# ETH_PHY_RMII.net
KiCad netlist of a schematic drawn in Altium Designer
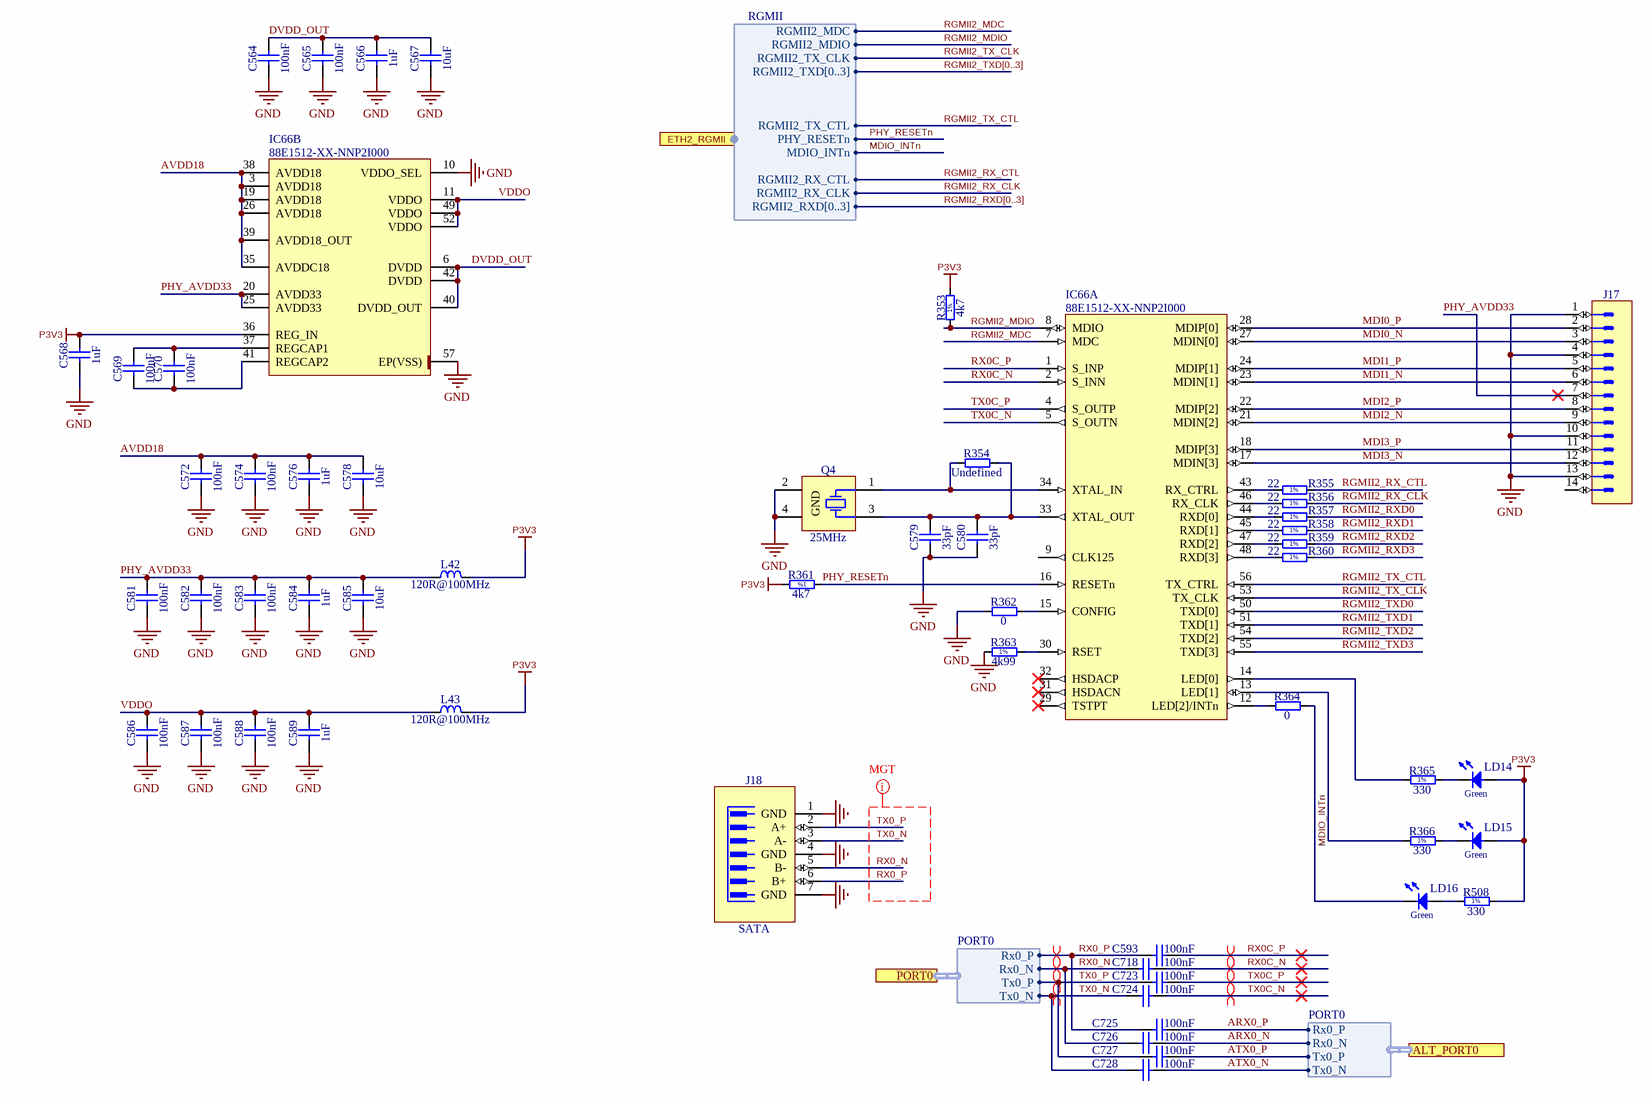
[diagram p0: ETH_PHY_RMII.SchDoc]

(export (version "E")
  (design (tool "Eeschema 10.0.6"))
  (components
    (comp (ref "C564")
      (value "100nF")
      (footprint "CAPC0603X33N")
      (description "Non-polarised capacitor")
      (fields
        (field (name "MANUFACTURER PART NUMBER") "CC0201_100NF_6.3V_10%_X5R")
        (field (name "MANUFACTURER") "GENERIC")
        (field (name "AUTHOR") "CERN DEM JLC")
      )
      (libsource (lib "Capacitors") (part "Capacitor - non polarized"))
    )
    (comp (ref "C565")
      (value "100nF")
      (footprint "CAPC0603X33N")
      (description "Non-polarised capacitor")
      (fields
        (field (name "MANUFACTURER PART NUMBER") "CC0201_100NF_6.3V_10%_X5R")
        (field (name "MANUFACTURER") "GENERIC")
        (field (name "AUTHOR") "CERN DEM JLC")
      )
      (libsource (lib "Capacitors") (part "Capacitor - non polarized"))
    )
    (comp (ref "C566")
      (value "1uF")
      (footprint "CAPC1005X55N")
      (description "Non-polarised capacitor")
      (fields
        (field (name "MANUFACTURER PART NUMBER") "CC0402_1UF_16V_10%_X5R")
        (field (name "MANUFACTURER") "GENERIC")
        (field (name "AUTHOR") "CERN DEM JLC")
      )
      (libsource (lib "Capacitors") (part "Capacitor - non polarized"))
    )
    (comp (ref "C567")
      (value "10uF")
      (footprint "CAPC1608X87N")
      (description "Non-polarised capacitor")
      (fields
        (field (name "MANUFACTURER PART NUMBER") "CC0603_10uF_6.3V_20%_X5R")
        (field (name "MANUFACTURER") "GENERIC")
        (field (name "AUTHOR") "CERN DEM JLC")
      )
      (libsource (lib "Capacitors") (part "Capacitor - non polarized"))
    )
    (comp (ref "C568")
      (value "1uF")
      (footprint "CAPC1005X55N")
      (description "Non-polarised capacitor")
      (fields
        (field (name "MANUFACTURER PART NUMBER") "CC0402_1UF_16V_10%_X5R")
        (field (name "MANUFACTURER") "GENERIC")
        (field (name "AUTHOR") "CERN DEM JLC")
      )
      (libsource (lib "Capacitors") (part "Capacitor - non polarized"))
    )
    (comp (ref "C569")
      (value "100nF")
      (footprint "CAPC0603X33N")
      (description "Non-polarised capacitor")
      (fields
        (field (name "MANUFACTURER PART NUMBER") "CC0201_100NF_6.3V_10%_X5R")
        (field (name "MANUFACTURER") "GENERIC")
        (field (name "AUTHOR") "CERN DEM JLC")
      )
      (libsource (lib "Capacitors") (part "Capacitor - non polarized"))
    )
    (comp (ref "C570")
      (value "100nF")
      (footprint "CAPC0603X33N")
      (description "Non-polarised capacitor")
      (fields
        (field (name "MANUFACTURER PART NUMBER") "CC0201_100NF_6.3V_10%_X5R")
        (field (name "MANUFACTURER") "GENERIC")
        (field (name "AUTHOR") "CERN DEM JLC")
      )
      (libsource (lib "Capacitors") (part "Capacitor - non polarized"))
    )
    (comp (ref "C572")
      (value "100nF")
      (footprint "CAPC0603X33N")
      (description "Non-polarised capacitor")
      (fields
        (field (name "MANUFACTURER PART NUMBER") "CC0201_100NF_6.3V_10%_X5R")
        (field (name "MANUFACTURER") "GENERIC")
        (field (name "AUTHOR") "CERN DEM JLC")
      )
      (libsource (lib "Capacitors") (part "Capacitor - non polarized"))
    )
    (comp (ref "C574")
      (value "100nF")
      (footprint "CAPC0603X33N")
      (description "Non-polarised capacitor")
      (fields
        (field (name "MANUFACTURER PART NUMBER") "CC0201_100NF_6.3V_10%_X5R")
        (field (name "MANUFACTURER") "GENERIC")
        (field (name "AUTHOR") "CERN DEM JLC")
      )
      (libsource (lib "Capacitors") (part "Capacitor - non polarized"))
    )
    (comp (ref "C576")
      (value "1uF")
      (footprint "CAPC1005X55N")
      (description "Non-polarised capacitor")
      (fields
        (field (name "MANUFACTURER PART NUMBER") "CC0402_1UF_16V_10%_X5R")
        (field (name "MANUFACTURER") "GENERIC")
        (field (name "AUTHOR") "CERN DEM JLC")
      )
      (libsource (lib "Capacitors") (part "Capacitor - non polarized"))
    )
    (comp (ref "C578")
      (value "10uF")
      (footprint "CAPC1608X87N")
      (description "Non-polarised capacitor")
      (fields
        (field (name "MANUFACTURER PART NUMBER") "CC0603_10uF_6.3V_20%_X5R")
        (field (name "MANUFACTURER") "GENERIC")
        (field (name "AUTHOR") "CERN DEM JLC")
      )
      (libsource (lib "Capacitors") (part "Capacitor - non polarized"))
    )
    (comp (ref "C579")
      (value "33pF")
      (footprint "CAPC1005X55N")
      (description "Non-polarised capacitor")
      (fields
        (field (name "PART NUMBER") "CC0402_33PF_50V_5%_C0G")
        (field (name "VOLTAGE") "50V")
        (field (name "AUTHOR") "CERN DEM JLC")
      )
      (libsource (lib "Capacitors") (part "Capacitor - non polarized"))
    )
    (comp (ref "C580")
      (value "33pF")
      (footprint "CAPC1005X55N")
      (description "Non-polarised capacitor")
      (fields
        (field (name "PART NUMBER") "CC0402_33PF_50V_5%_C0G")
        (field (name "VOLTAGE") "50V")
        (field (name "AUTHOR") "CERN DEM JLC")
      )
      (libsource (lib "Capacitors") (part "Capacitor - non polarized"))
    )
    (comp (ref "C581")
      (value "100nF")
      (footprint "CAPC0603X33N")
      (description "Non-polarised capacitor")
      (fields
        (field (name "MANUFACTURER PART NUMBER") "CC0201_100NF_6.3V_10%_X5R")
        (field (name "MANUFACTURER") "GENERIC")
        (field (name "AUTHOR") "CERN DEM JLC")
      )
      (libsource (lib "Capacitors") (part "Capacitor - non polarized"))
    )
    (comp (ref "C582")
      (value "100nF")
      (footprint "CAPC0603X33N")
      (description "Non-polarised capacitor")
      (fields
        (field (name "MANUFACTURER PART NUMBER") "CC0201_100NF_6.3V_10%_X5R")
        (field (name "MANUFACTURER") "GENERIC")
        (field (name "AUTHOR") "CERN DEM JLC")
      )
      (libsource (lib "Capacitors") (part "Capacitor - non polarized"))
    )
    (comp (ref "C583")
      (value "100nF")
      (footprint "CAPC0603X33N")
      (description "Non-polarised capacitor")
      (fields
        (field (name "MANUFACTURER PART NUMBER") "CC0201_100NF_6.3V_10%_X5R")
        (field (name "MANUFACTURER") "GENERIC")
        (field (name "AUTHOR") "CERN DEM JLC")
      )
      (libsource (lib "Capacitors") (part "Capacitor - non polarized"))
    )
    (comp (ref "C584")
      (value "1uF")
      (footprint "CAPC1005X55N")
      (description "Non-polarised capacitor")
      (fields
        (field (name "MANUFACTURER PART NUMBER") "CC0402_1UF_16V_10%_X5R")
        (field (name "MANUFACTURER") "GENERIC")
        (field (name "AUTHOR") "CERN DEM JLC")
      )
      (libsource (lib "Capacitors") (part "Capacitor - non polarized"))
    )
    (comp (ref "C585")
      (value "10uF")
      (footprint "CAPC1608X87N")
      (description "Non-polarised capacitor")
      (fields
        (field (name "MANUFACTURER PART NUMBER") "CC0603_10uF_6.3V_20%_X5R")
        (field (name "MANUFACTURER") "GENERIC")
        (field (name "AUTHOR") "CERN DEM JLC")
      )
      (libsource (lib "Capacitors") (part "Capacitor - non polarized"))
    )
    (comp (ref "C586")
      (value "100nF")
      (footprint "CAPC0603X33N")
      (description "Non-polarised capacitor")
      (fields
        (field (name "MANUFACTURER PART NUMBER") "CC0201_100NF_6.3V_10%_X5R")
        (field (name "MANUFACTURER") "GENERIC")
        (field (name "AUTHOR") "CERN DEM JLC")
      )
      (libsource (lib "Capacitors") (part "Capacitor - non polarized"))
    )
    (comp (ref "C587")
      (value "100nF")
      (footprint "CAPC0603X33N")
      (description "Non-polarised capacitor")
      (fields
        (field (name "MANUFACTURER PART NUMBER") "CC0201_100NF_6.3V_10%_X5R")
        (field (name "MANUFACTURER") "GENERIC")
        (field (name "AUTHOR") "CERN DEM JLC")
      )
      (libsource (lib "Capacitors") (part "Capacitor - non polarized"))
    )
    (comp (ref "C588")
      (value "100nF")
      (footprint "CAPC0603X33N")
      (description "Non-polarised capacitor")
      (fields
        (field (name "MANUFACTURER PART NUMBER") "CC0201_100NF_6.3V_10%_X5R")
        (field (name "MANUFACTURER") "GENERIC")
        (field (name "AUTHOR") "CERN DEM JLC")
      )
      (libsource (lib "Capacitors") (part "Capacitor - non polarized"))
    )
    (comp (ref "C589")
      (value "1uF")
      (footprint "CAPC1005X55N")
      (description "Non-polarised capacitor")
      (fields
        (field (name "MANUFACTURER PART NUMBER") "CC0402_1UF_16V_10%_X5R")
        (field (name "MANUFACTURER") "GENERIC")
        (field (name "AUTHOR") "CERN DEM JLC")
      )
      (libsource (lib "Capacitors") (part "Capacitor - non polarized"))
    )
    (comp (ref "C593")
      (value "100nF")
      (footprint "CAPC0603X33N")
      (description "Non-polarised capacitor")
      (fields
        (field (name "MANUFACTURER PART NUMBER") "CC0201_100NF_6.3V_10%_X5R")
        (field (name "MANUFACTURER") "GENERIC")
        (field (name "AUTHOR") "CERN DEM JLC")
      )
      (libsource (lib "Capacitors") (part "Capacitor - non polarized"))
    )
    (comp (ref "C718")
      (value "100nF")
      (footprint "CAPC0603X33N")
      (description "Non-polarised capacitor")
      (fields
        (field (name "MANUFACTURER PART NUMBER") "CC0201_100NF_6.3V_10%_X5R")
        (field (name "MANUFACTURER") "GENERIC")
        (field (name "AUTHOR") "CERN DEM JLC")
      )
      (libsource (lib "Capacitors") (part "Capacitor - non polarized"))
    )
    (comp (ref "C723")
      (value "100nF")
      (footprint "CAPC0603X33N")
      (description "Non-polarised capacitor")
      (fields
        (field (name "MANUFACTURER PART NUMBER") "CC0201_100NF_6.3V_10%_X5R")
        (field (name "MANUFACTURER") "GENERIC")
        (field (name "AUTHOR") "CERN DEM JLC")
      )
      (libsource (lib "Capacitors") (part "Capacitor - non polarized"))
    )
    (comp (ref "C724")
      (value "100nF")
      (footprint "CAPC0603X33N")
      (description "Non-polarised capacitor")
      (fields
        (field (name "MANUFACTURER PART NUMBER") "CC0201_100NF_6.3V_10%_X5R")
        (field (name "MANUFACTURER") "GENERIC")
        (field (name "AUTHOR") "CERN DEM JLC")
      )
      (libsource (lib "Capacitors") (part "Capacitor - non polarized"))
    )
    (comp (ref "C725")
      (value "100nF")
      (footprint "CAPC0603X33N")
      (description "Non-polarised capacitor")
      (fields
        (field (name "MANUFACTURER PART NUMBER") "CC0201_100NF_6.3V_10%_X5R")
        (field (name "MANUFACTURER") "GENERIC")
        (field (name "AUTHOR") "CERN DEM JLC")
      )
      (libsource (lib "Capacitors") (part "Capacitor - non polarized"))
    )
    (comp (ref "C726")
      (value "100nF")
      (footprint "CAPC0603X33N")
      (description "Non-polarised capacitor")
      (fields
        (field (name "MANUFACTURER PART NUMBER") "CC0201_100NF_6.3V_10%_X5R")
        (field (name "MANUFACTURER") "GENERIC")
        (field (name "AUTHOR") "CERN DEM JLC")
      )
      (libsource (lib "Capacitors") (part "Capacitor - non polarized"))
    )
    (comp (ref "C727")
      (value "100nF")
      (footprint "CAPC0603X33N")
      (description "Non-polarised capacitor")
      (fields
        (field (name "MANUFACTURER PART NUMBER") "CC0201_100NF_6.3V_10%_X5R")
        (field (name "MANUFACTURER") "GENERIC")
        (field (name "AUTHOR") "CERN DEM JLC")
      )
      (libsource (lib "Capacitors") (part "Capacitor - non polarized"))
    )
    (comp (ref "C728")
      (value "100nF")
      (footprint "CAPC0603X33N")
      (description "Non-polarised capacitor")
      (fields
        (field (name "MANUFACTURER PART NUMBER") "CC0201_100NF_6.3V_10%_X5R")
        (field (name "MANUFACTURER") "GENERIC")
        (field (name "AUTHOR") "CERN DEM JLC")
      )
      (libsource (lib "Capacitors") (part "Capacitor - non polarized"))
    )
    (comp (ref "IC66")
      (value "88E1512-XX-NNP2I000")
      (footprint "QFN50P800X800X100-57N-S437")
      (description "Alaska Integrated 10/100/1000 Mbps Energy Efficient Ethernet Transceiver")
      (fields (field (name "MANUFACTURER") "MARVELL  TECHNOLOGY") (field (name "AUTHOR") "CERN DEM JLC"))
      (libsource (lib "ICs And Semiconductors") (part "88E1512-XX-NNP2I000"))
    )
    (comp (ref "J17")
      (value "Milli-Grid™")
      (footprint "MOLEX_87832-1420")
      (description "Connector 14 Male")
      (fields
        (field (name "PART NUMBER") "MOLEX_87832-1420")
        (field (name "MANUFACTURER") "MOLEX")
        (field (name "AUTHOR") "CERN DEM JLC")
      )
      (libsource (lib "Connectors") (part "Connector 14 Male"))
    )
    (comp (ref "J18")
      (value "SATA")
      (footprint "MOLEX_67800-5005")
      (description "7 Pin SATA Receptacle")
      (fields
        (field (name "PART NUMBER") "MOLEX_67800-5005")
        (field (name "MANUFACTURER") "MOLEX")
        (field (name "AUTHOR") "CERN DEM MR")
      )
      (libsource (lib "Connectors") (part "Connector SATA 7 Male"))
    )
    (comp (ref "L42")
      (value "120R@100MHz")
      (footprint "INDC1005X55N")
      (description "Inductor")
      (fields
        (field (name "MANUFACTURER PART NUMBER") "BLM15PX121SN1D")
        (field (name "MANUFACTURER") "MURATA")
        (field (name "AUTHOR") "CERN DEM JMW")
      )
      (libsource (lib "Inductors & Transformers") (part "Inductor"))
    )
    (comp (ref "L43")
      (value "120R@100MHz")
      (footprint "INDC1005X55N")
      (description "Inductor")
      (fields
        (field (name "MANUFACTURER PART NUMBER") "BLM15PX121SN1D")
        (field (name "MANUFACTURER") "MURATA")
        (field (name "AUTHOR") "CERN DEM JMW")
      )
      (libsource (lib "Inductors & Transformers") (part "Inductor"))
    )
    (comp (ref "LD14")
      (value "Green")
      (footprint "LED_OSRAM_LGL29K")
      (description "LED Green 1C 2A")
      (fields
        (field (name "MANUFACTURER PART NUMBER") "LG L29K-G2J1-24-Z")
        (field (name "MANUFACTURER") "OSRAM")
        (field (name "AUTHOR") "CERN DEM JLC")
      )
      (libsource (lib "ICs And Semiconductors") (part "LED Green 1C 2A"))
    )
    (comp (ref "LD15")
      (value "Green")
      (footprint "LED_OSRAM_LGL29K")
      (description "LED Green 1C 2A")
      (fields
        (field (name "MANUFACTURER PART NUMBER") "LG L29K-G2J1-24-Z")
        (field (name "MANUFACTURER") "OSRAM")
        (field (name "AUTHOR") "CERN DEM JLC")
      )
      (libsource (lib "ICs And Semiconductors") (part "LED Green 1C 2A"))
    )
    (comp (ref "LD16")
      (value "Green")
      (footprint "LED_OSRAM_LGL29K")
      (description "LED Green 1C 2A")
      (fields
        (field (name "MANUFACTURER PART NUMBER") "LG L29K-G2J1-24-Z")
        (field (name "MANUFACTURER") "OSRAM")
        (field (name "AUTHOR") "CERN DEM JLC")
      )
      (libsource (lib "ICs And Semiconductors") (part "LED Green 1C 2A"))
    )
    (comp (ref "Q4")
      (value "25MHz")
      (footprint "XTAL_TXC_8Y")
      (description "Crystal 4 pins 1=XTAL Control 2=GND3=XTAL 4=GND")
      (fields
        (field (name "PART NUMBER") "XTAL_25MHZ_TXC_8Y-25.000MAAJ-T")
        (field (name "MANUFACTURER") "TXC CORPORATION")
        (field (name "AUTHOR") "CERN DEM JLC")
      )
      (libsource (lib "ICs And Semiconductors") (part "Quartz Crystal 1X 2GND 3X 4GND"))
    )
    (comp (ref "R353")
      (value "4k7")
      (footprint "RESC1005X40N")
      (description "Resistor - 1%")
      (fields
        (field (name "PART NUMBER") "R0402_4K7_1%_0.0625W_100PPM")
        (field (name "POWER") "0.0625W")
        (field (name "AUTHOR") "CERN DEM JLC")
      )
      (libsource (lib "Resistors") (part "Resistor - 1%"))
    )
    (comp (ref "R354")
      (value "Undefined")
      (footprint "RESC1005X40N")
      (description "Resistor")
      (fields
        (field (name "MANUFACTURER PART NUMBER") "R0402_0R_JUMPER")
        (field (name "MANUFACTURER") "GENERIC")
        (field (name "AUTHOR") "CERN DEM JLC")
      )
      (libsource (lib "Resistors") (part "Resistor"))
    )
    (comp (ref "R355")
      (value "22")
      (footprint "RESC1005X40N")
      (description "Resistor - 1%")
      (fields
        (field (name "PART NUMBER") "R0402_22R_1%_0.0625W_100PPM")
        (field (name "POWER") "0.0625W")
        (field (name "AUTHOR") "CERN DEM JLC")
      )
      (libsource (lib "Resistors") (part "Resistor - 1%"))
    )
    (comp (ref "R356")
      (value "22")
      (footprint "RESC1005X40N")
      (description "Resistor - 1%")
      (fields
        (field (name "PART NUMBER") "R0402_22R_1%_0.0625W_100PPM")
        (field (name "POWER") "0.0625W")
        (field (name "AUTHOR") "CERN DEM JLC")
      )
      (libsource (lib "Resistors") (part "Resistor - 1%"))
    )
    (comp (ref "R357")
      (value "22")
      (footprint "RESC1005X40N")
      (description "Resistor - 1%")
      (fields
        (field (name "PART NUMBER") "R0402_22R_1%_0.0625W_100PPM")
        (field (name "POWER") "0.0625W")
        (field (name "AUTHOR") "CERN DEM JLC")
      )
      (libsource (lib "Resistors") (part "Resistor - 1%"))
    )
    (comp (ref "R358")
      (value "22")
      (footprint "RESC1005X40N")
      (description "Resistor - 1%")
      (fields
        (field (name "PART NUMBER") "R0402_22R_1%_0.0625W_100PPM")
        (field (name "POWER") "0.0625W")
        (field (name "AUTHOR") "CERN DEM JLC")
      )
      (libsource (lib "Resistors") (part "Resistor - 1%"))
    )
    (comp (ref "R359")
      (value "22")
      (footprint "RESC1005X40N")
      (description "Resistor - 1%")
      (fields
        (field (name "PART NUMBER") "R0402_22R_1%_0.0625W_100PPM")
        (field (name "POWER") "0.0625W")
        (field (name "AUTHOR") "CERN DEM JLC")
      )
      (libsource (lib "Resistors") (part "Resistor - 1%"))
    )
    (comp (ref "R360")
      (value "22")
      (footprint "RESC1005X40N")
      (description "Resistor - 1%")
      (fields
        (field (name "PART NUMBER") "R0402_22R_1%_0.0625W_100PPM")
        (field (name "POWER") "0.0625W")
        (field (name "AUTHOR") "CERN DEM JLC")
      )
      (libsource (lib "Resistors") (part "Resistor - 1%"))
    )
    (comp (ref "R361")
      (value "4k7")
      (footprint "RESC1005X40N")
      (description "Resistor - 1%")
      (fields
        (field (name "MANUFACTURER PART NUMBER") "R0402_4K7_1%_0.0625W_100PPM")
        (field (name "MANUFACTURER") "GENERIC")
        (field (name "AUTHOR") "CERN DEM JLC")
      )
      (libsource (lib "Resistors") (part "Resistor - 1%"))
    )
    (comp (ref "R362")
      (value "0")
      (footprint "RESC1005X40N")
      (description "Resistor")
      (fields
        (field (name "MANUFACTURER PART NUMBER") "R0402_0R_JUMPER")
        (field (name "MANUFACTURER") "GENERIC")
        (field (name "AUTHOR") "CERN DEM JLC")
      )
      (libsource (lib "Resistors") (part "Resistor"))
    )
    (comp (ref "R363")
      (value "4k99")
      (footprint "RESC1608X55N")
      (description "Resistor - 1%")
      (fields
        (field (name "MANUFACTURER PART NUMBER") "R0603_4K99_1%_0.063W_50PPM")
        (field (name "MANUFACTURER") "GENERIC")
        (field (name "AUTHOR") "CERN DEM JLC")
      )
      (libsource (lib "Resistors") (part "Resistor - 1%"))
    )
    (comp (ref "R364")
      (value "0")
      (footprint "RESC1005X40N")
      (description "Resistor")
      (fields
        (field (name "MANUFACTURER PART NUMBER") "R0402_0R_JUMPER")
        (field (name "MANUFACTURER") "GENERIC")
        (field (name "AUTHOR") "CERN DEM JLC")
      )
      (libsource (lib "Resistors") (part "Resistor"))
    )
    (comp (ref "R365")
      (value "330")
      (footprint "RESC1005X40N")
      (description "Resistor - 1%")
      (fields
        (field (name "MANUFACTURER PART NUMBER") "R0402_330R_1%_0.0625W_100PPM")
        (field (name "MANUFACTURER") "GENERIC")
        (field (name "AUTHOR") "CERN DEM JLC")
      )
      (libsource (lib "Resistors") (part "Resistor - 1%"))
    )
    (comp (ref "R366")
      (value "330")
      (footprint "RESC1005X40N")
      (description "Resistor - 1%")
      (fields
        (field (name "MANUFACTURER PART NUMBER") "R0402_330R_1%_0.0625W_100PPM")
        (field (name "MANUFACTURER") "GENERIC")
        (field (name "AUTHOR") "CERN DEM JLC")
      )
      (libsource (lib "Resistors") (part "Resistor - 1%"))
    )
    (comp (ref "R508")
      (value "330")
      (footprint "RESC1005X40N")
      (description "Resistor - 1%")
      (fields
        (field (name "MANUFACTURER PART NUMBER") "R0402_330R_1%_0.0625W_100PPM")
        (field (name "MANUFACTURER") "GENERIC")
        (field (name "AUTHOR") "CERN DEM JLC")
      )
      (libsource (lib "Resistors") (part "Resistor - 1%"))
    )
  )
  (nets
    (net (code "3") (name "/ARX0_N") (class "Default")
      (node (ref "C726") (pin "2") (pinfunction "2_2") (pintype "passive"))
    )
    (net (code "4") (name "/ARX0_P") (class "Default")
      (node (ref "C725") (pin "2") (pinfunction "2_2") (pintype "passive"))
    )
    (net (code "5") (name "/ATX0_N") (class "Default")
      (node (ref "C728") (pin "2") (pinfunction "2_2") (pintype "passive"))
    )
    (net (code "6") (name "/ATX0_P") (class "Default")
      (node (ref "C727") (pin "2") (pinfunction "2_2") (pintype "passive"))
    )
    (net (code "7") (name "/AVDD18") (class "Default")
      (node (ref "C572") (pin "2") (pinfunction "2_2") (pintype "passive"))
      (node (ref "C574") (pin "2") (pinfunction "2_2") (pintype "passive"))
      (node (ref "C576") (pin "2") (pinfunction "2_2") (pintype "passive"))
      (node (ref "C578") (pin "2") (pinfunction "2_2") (pintype "passive"))
      (node (ref "IC66") (pin "19") (pinfunction "AVDD18_19") (pintype "power_in"))
      (node (ref "IC66") (pin "26") (pinfunction "AVDD18_26") (pintype "power_in"))
      (node (ref "IC66") (pin "3") (pinfunction "AVDD18_3") (pintype "power_in"))
      (node (ref "IC66") (pin "35") (pinfunction "AVDDC18_35") (pintype "power_in"))
      (node (ref "IC66") (pin "38") (pinfunction "AVDD18_38") (pintype "power_in"))
      (node (ref "IC66") (pin "39") (pinfunction "AVDD18_OUT_39") (pintype "power_in"))
    )
    (net (code "8") (name "/DVDD_OUT") (class "Default")
      (node (ref "C564") (pin "2") (pinfunction "2_2") (pintype "passive"))
      (node (ref "C565") (pin "2") (pinfunction "2_2") (pintype "passive"))
      (node (ref "C566") (pin "2") (pinfunction "2_2") (pintype "passive"))
      (node (ref "C567") (pin "2") (pinfunction "2_2") (pintype "passive"))
      (node (ref "IC66") (pin "40") (pinfunction "DVDD_OUT_40") (pintype "power_in"))
      (node (ref "IC66") (pin "42") (pinfunction "DVDD_42") (pintype "power_in"))
      (node (ref "IC66") (pin "6") (pinfunction "DVDD_6") (pintype "power_in"))
    )
    (net (code "10") (name "/MDI0_N") (class "Default")
      (node (ref "IC66") (pin "27") (pinfunction "MDIN[0]_27") (pintype "bidirectional"))
      (node (ref "J17") (pin "3") (pinfunction "3_3") (pintype "bidirectional"))
    )
    (net (code "11") (name "/MDI0_P") (class "Default")
      (node (ref "IC66") (pin "28") (pinfunction "MDIP[0]_28") (pintype "bidirectional"))
      (node (ref "J17") (pin "2") (pinfunction "2_2") (pintype "bidirectional"))
    )
    (net (code "12") (name "/MDI1_N") (class "Default")
      (node (ref "IC66") (pin "23") (pinfunction "MDIN[1]_23") (pintype "bidirectional"))
      (node (ref "J17") (pin "6") (pinfunction "6_6") (pintype "bidirectional"))
    )
    (net (code "13") (name "/MDI1_P") (class "Default")
      (node (ref "IC66") (pin "24") (pinfunction "MDIP[1]_24") (pintype "bidirectional"))
      (node (ref "J17") (pin "5") (pinfunction "5_5") (pintype "bidirectional"))
    )
    (net (code "14") (name "/MDI2_N") (class "Default")
      (node (ref "IC66") (pin "21") (pinfunction "MDIN[2]_21") (pintype "bidirectional"))
      (node (ref "J17") (pin "9") (pinfunction "9_9") (pintype "bidirectional"))
    )
    (net (code "15") (name "/MDI2_P") (class "Default")
      (node (ref "IC66") (pin "22") (pinfunction "MDIP[2]_22") (pintype "bidirectional"))
      (node (ref "J17") (pin "8") (pinfunction "8_8") (pintype "bidirectional"))
    )
    (net (code "16") (name "/MDI3_N") (class "Default")
      (node (ref "IC66") (pin "17") (pinfunction "MDIN[3]_17") (pintype "bidirectional"))
      (node (ref "J17") (pin "12") (pinfunction "12_12") (pintype "bidirectional"))
    )
    (net (code "17") (name "/MDI3_P") (class "Default")
      (node (ref "IC66") (pin "18") (pinfunction "MDIP[3]_18") (pintype "bidirectional"))
      (node (ref "J17") (pin "11") (pinfunction "11_11") (pintype "bidirectional"))
    )
    (net (code "18") (name "/MDIO_INTn") (class "Default")
      (node (ref "LD16") (pin "1") (pinfunction "C_1") (pintype "passive"))
      (node (ref "R364") (pin "2") (pinfunction "2_2") (pintype "passive"))
    )
    (net (code "19") (name "/PHY_AVDD33") (class "Default")
      (node (ref "C581") (pin "2") (pinfunction "2_2") (pintype "passive"))
      (node (ref "C582") (pin "2") (pinfunction "2_2") (pintype "passive"))
      (node (ref "C583") (pin "2") (pinfunction "2_2") (pintype "passive"))
      (node (ref "C584") (pin "2") (pinfunction "2_2") (pintype "passive"))
      (node (ref "C585") (pin "2") (pinfunction "2_2") (pintype "passive"))
      (node (ref "IC66") (pin "20") (pinfunction "AVDD33_20") (pintype "power_in"))
      (node (ref "IC66") (pin "25") (pinfunction "AVDD33_25") (pintype "power_in"))
      (node (ref "J17") (pin "7") (pinfunction "7_7") (pintype "bidirectional"))
      (node (ref "L42") (pin "1") (pinfunction "1_1") (pintype "passive"))
    )
    (net (code "20") (name "/PHY_RESETn") (class "Default")
      (node (ref "IC66") (pin "16") (pinfunction "RESETn_16") (pintype "input"))
      (node (ref "R361") (pin "1") (pinfunction "1_1") (pintype "passive"))
    )
    (net (code "21") (name "/RGMII2_MDC") (class "Default")
      (node (ref "IC66") (pin "7") (pinfunction "MDC_7") (pintype "input"))
    )
    (net (code "22") (name "/RGMII2_MDIO") (class "Default")
      (node (ref "IC66") (pin "8") (pinfunction "MDIO_8") (pintype "bidirectional"))
      (node (ref "R353") (pin "1") (pinfunction "1_1") (pintype "passive"))
    )
    (net (code "23") (name "/RGMII2_RXD0") (class "Default")
      (node (ref "R357") (pin "2") (pinfunction "2_2") (pintype "passive"))
    )
    (net (code "24") (name "/RGMII2_RXD1") (class "Default")
      (node (ref "R358") (pin "2") (pinfunction "2_2") (pintype "passive"))
    )
    (net (code "25") (name "/RGMII2_RXD2") (class "Default")
      (node (ref "R359") (pin "2") (pinfunction "2_2") (pintype "passive"))
    )
    (net (code "26") (name "/RGMII2_RXD3") (class "Default")
      (node (ref "R360") (pin "2") (pinfunction "2_2") (pintype "passive"))
    )
    (net (code "28") (name "/RGMII2_RX_CLK") (class "Default")
      (node (ref "R356") (pin "2") (pinfunction "2_2") (pintype "passive"))
    )
    (net (code "29") (name "/RGMII2_RX_CTL") (class "Default")
      (node (ref "R355") (pin "2") (pinfunction "2_2") (pintype "passive"))
    )
    (net (code "30") (name "/RGMII2_TXD0") (class "Default")
      (node (ref "IC66") (pin "50") (pinfunction "TXD[0]_50") (pintype "input"))
    )
    (net (code "31") (name "/RGMII2_TXD1") (class "Default")
      (node (ref "IC66") (pin "51") (pinfunction "TXD[1]_51") (pintype "input"))
    )
    (net (code "32") (name "/RGMII2_TXD2") (class "Default")
      (node (ref "IC66") (pin "54") (pinfunction "TXD[2]_54") (pintype "input"))
    )
    (net (code "33") (name "/RGMII2_TXD3") (class "Default")
      (node (ref "IC66") (pin "55") (pinfunction "TXD[3]_55") (pintype "input"))
    )
    (net (code "34") (name "/RGMII2_TX_CLK") (class "Default")
      (node (ref "IC66") (pin "53") (pinfunction "TX_CLK_53") (pintype "input"))
    )
    (net (code "35") (name "/RGMII2_TX_CTL") (class "Default")
      (node (ref "IC66") (pin "56") (pinfunction "TX_CTRL_56") (pintype "input"))
    )
    (net (code "36") (name "/RX0C_N") (class "Default")
      (node (ref "C718") (pin "2") (pinfunction "2_2") (pintype "passive"))
      (node (ref "IC66") (pin "2") (pinfunction "S_INN_2") (pintype "input"))
    )
    (net (code "37") (name "/RX0C_P") (class "Default")
      (node (ref "C593") (pin "2") (pinfunction "2_2") (pintype "passive"))
      (node (ref "IC66") (pin "1") (pinfunction "S_INP_1") (pintype "input"))
    )
    (net (code "38") (name "/RX0_N") (class "Default")
      (node (ref "C718") (pin "1") (pinfunction "1_1") (pintype "passive"))
      (node (ref "C726") (pin "1") (pinfunction "1_1") (pintype "passive"))
      (node (ref "J18") (pin "5") (pinfunction "B-_5") (pintype "bidirectional"))
    )
    (net (code "39") (name "/RX0_P") (class "Default")
      (node (ref "C593") (pin "1") (pinfunction "1_1") (pintype "passive"))
      (node (ref "C725") (pin "1") (pinfunction "1_1") (pintype "passive"))
      (node (ref "J18") (pin "6") (pinfunction "B+_6") (pintype "bidirectional"))
    )
    (net (code "40") (name "/TX0C_N") (class "Default")
      (node (ref "C724") (pin "2") (pinfunction "2_2") (pintype "passive"))
      (node (ref "IC66") (pin "5") (pinfunction "S_OUTN_5") (pintype "output"))
    )
    (net (code "41") (name "/TX0C_P") (class "Default")
      (node (ref "C723") (pin "2") (pinfunction "2_2") (pintype "passive"))
      (node (ref "IC66") (pin "4") (pinfunction "S_OUTP_4") (pintype "output"))
    )
    (net (code "42") (name "/TX0_N") (class "Default")
      (node (ref "C724") (pin "1") (pinfunction "1_1") (pintype "passive"))
      (node (ref "C728") (pin "1") (pinfunction "1_1") (pintype "passive"))
      (node (ref "J18") (pin "3") (pinfunction "A-_3") (pintype "bidirectional"))
    )
    (net (code "43") (name "/TX0_P") (class "Default")
      (node (ref "C723") (pin "1") (pinfunction "1_1") (pintype "passive"))
      (node (ref "C727") (pin "1") (pinfunction "1_1") (pintype "passive"))
      (node (ref "J18") (pin "2") (pinfunction "A+_2") (pintype "bidirectional"))
    )
    (net (code "44") (name "/VDDO") (class "Default")
      (node (ref "C586") (pin "2") (pinfunction "2_2") (pintype "passive"))
      (node (ref "C587") (pin "2") (pinfunction "2_2") (pintype "passive"))
      (node (ref "C588") (pin "2") (pinfunction "2_2") (pintype "passive"))
      (node (ref "C589") (pin "2") (pinfunction "2_2") (pintype "passive"))
      (node (ref "IC66") (pin "11") (pinfunction "VDDO_11") (pintype "power_in"))
      (node (ref "IC66") (pin "49") (pinfunction "VDDO_49") (pintype "power_in"))
      (node (ref "IC66") (pin "52") (pinfunction "VDDO_52") (pintype "power_in"))
      (node (ref "L43") (pin "1") (pinfunction "1_1") (pintype "passive"))
    )
    (net (code "47") (name "GND") (class "Default")
      (node (ref "C564") (pin "1") (pinfunction "1_1") (pintype "passive"))
      (node (ref "C565") (pin "1") (pinfunction "1_1") (pintype "passive"))
      (node (ref "C566") (pin "1") (pinfunction "1_1") (pintype "passive"))
      (node (ref "C567") (pin "1") (pinfunction "1_1") (pintype "passive"))
      (node (ref "C568") (pin "1") (pinfunction "1_1") (pintype "passive"))
      (node (ref "C572") (pin "1") (pinfunction "1_1") (pintype "passive"))
      (node (ref "C574") (pin "1") (pinfunction "1_1") (pintype "passive"))
      (node (ref "C576") (pin "1") (pinfunction "1_1") (pintype "passive"))
      (node (ref "C578") (pin "1") (pinfunction "1_1") (pintype "passive"))
      (node (ref "C579") (pin "1") (pinfunction "1_1") (pintype "passive"))
      (node (ref "C580") (pin "1") (pinfunction "1_1") (pintype "passive"))
      (node (ref "C581") (pin "1") (pinfunction "1_1") (pintype "passive"))
      (node (ref "C582") (pin "1") (pinfunction "1_1") (pintype "passive"))
      (node (ref "C583") (pin "1") (pinfunction "1_1") (pintype "passive"))
      (node (ref "C584") (pin "1") (pinfunction "1_1") (pintype "passive"))
      (node (ref "C585") (pin "1") (pinfunction "1_1") (pintype "passive"))
      (node (ref "C586") (pin "1") (pinfunction "1_1") (pintype "passive"))
      (node (ref "C587") (pin "1") (pinfunction "1_1") (pintype "passive"))
      (node (ref "C588") (pin "1") (pinfunction "1_1") (pintype "passive"))
      (node (ref "C589") (pin "1") (pinfunction "1_1") (pintype "passive"))
      (node (ref "IC66") (pin "10") (pinfunction "VDDO_SEL_10") (pintype "power_in"))
      (node (ref "IC66") (pin "57") (pinfunction "EP(VSS)_57") (pintype "power_in"))
      (node (ref "J17") (pin "1") (pinfunction "1_1") (pintype "bidirectional"))
      (node (ref "J17") (pin "10") (pinfunction "10_10") (pintype "bidirectional"))
      (node (ref "J17") (pin "13") (pinfunction "13_13") (pintype "bidirectional"))
      (node (ref "J17") (pin "4") (pinfunction "4_4") (pintype "bidirectional"))
      (node (ref "J18") (pin "1") (pinfunction "GND_1") (pintype "power_in"))
      (node (ref "J18") (pin "4") (pinfunction "GND_4") (pintype "power_in"))
      (node (ref "J18") (pin "7") (pinfunction "GND_7") (pintype "power_in"))
      (node (ref "Q4") (pin "2") (pinfunction "GND_2") (pintype "power_in"))
      (node (ref "Q4") (pin "4") (pinfunction "GND_4") (pintype "power_in"))
      (node (ref "R362") (pin "1") (pinfunction "1_1") (pintype "passive"))
      (node (ref "R363") (pin "1") (pinfunction "1_1") (pintype "passive"))
    )
    (net (code "48") (name "Net-(IC66A-CONFIG)") (class "Default")
      (node (ref "IC66") (pin "15") (pinfunction "CONFIG_15") (pintype "input"))
      (node (ref "R362") (pin "2") (pinfunction "2_2") (pintype "passive"))
    )
    (net (code "49") (name "Net-(IC66A-LED[0])") (class "Default")
      (node (ref "IC66") (pin "14") (pinfunction "LED[0]_14") (pintype "output"))
      (node (ref "R365") (pin "1") (pinfunction "1_1") (pintype "passive"))
    )
    (net (code "50") (name "Net-(IC66A-LED[1])") (class "Default")
      (node (ref "IC66") (pin "13") (pinfunction "LED[1]_13") (pintype "bidirectional"))
      (node (ref "R366") (pin "1") (pinfunction "1_1") (pintype "passive"))
    )
    (net (code "51") (name "Net-(IC66A-LED[2]{slash}INTn)") (class "Default")
      (node (ref "IC66") (pin "12") (pinfunction "LED[2]/INTn_12") (pintype "output"))
      (node (ref "R364") (pin "1") (pinfunction "1_1") (pintype "passive"))
    )
    (net (code "52") (name "Net-(IC66A-RSET)") (class "Default")
      (node (ref "IC66") (pin "30") (pinfunction "RSET_30") (pintype "input"))
      (node (ref "R363") (pin "2") (pinfunction "2_2") (pintype "passive"))
    )
    (net (code "53") (name "Net-(IC66A-RXD[0])") (class "Default")
      (node (ref "IC66") (pin "44") (pinfunction "RXD[0]_44") (pintype "output"))
      (node (ref "R357") (pin "1") (pinfunction "1_1") (pintype "passive"))
    )
    (net (code "54") (name "Net-(IC66A-RXD[1])") (class "Default")
      (node (ref "IC66") (pin "45") (pinfunction "RXD[1]_45") (pintype "output"))
      (node (ref "R358") (pin "1") (pinfunction "1_1") (pintype "passive"))
    )
    (net (code "55") (name "Net-(IC66A-RXD[2])") (class "Default")
      (node (ref "IC66") (pin "47") (pinfunction "RXD[2]_47") (pintype "output"))
      (node (ref "R359") (pin "1") (pinfunction "1_1") (pintype "passive"))
    )
    (net (code "56") (name "Net-(IC66A-RXD[3])") (class "Default")
      (node (ref "IC66") (pin "48") (pinfunction "RXD[3]_48") (pintype "output"))
      (node (ref "R360") (pin "1") (pinfunction "1_1") (pintype "passive"))
    )
    (net (code "57") (name "Net-(IC66A-RX_CLK)") (class "Default")
      (node (ref "IC66") (pin "46") (pinfunction "RX_CLK_46") (pintype "output"))
      (node (ref "R356") (pin "1") (pinfunction "1_1") (pintype "passive"))
    )
    (net (code "58") (name "Net-(IC66A-RX_CTRL)") (class "Default")
      (node (ref "IC66") (pin "43") (pinfunction "RX_CTRL_43") (pintype "output"))
      (node (ref "R355") (pin "1") (pinfunction "1_1") (pintype "passive"))
    )
    (net (code "59") (name "Net-(IC66A-XTAL_IN)") (class "Default")
      (node (ref "IC66") (pin "34") (pinfunction "XTAL_IN_34") (pintype "input"))
      (node (ref "Q4") (pin "1") (pinfunction "X_1") (pintype "passive"))
      (node (ref "R354") (pin "1") (pinfunction "1_1") (pintype "passive"))
    )
    (net (code "60") (name "Net-(IC66A-XTAL_OUT)") (class "Default")
      (node (ref "C579") (pin "2") (pinfunction "2_2") (pintype "passive"))
      (node (ref "C580") (pin "2") (pinfunction "2_2") (pintype "passive"))
      (node (ref "IC66") (pin "33") (pinfunction "XTAL_OUT_33") (pintype "output"))
      (node (ref "Q4") (pin "3") (pinfunction "X_3") (pintype "passive"))
      (node (ref "R354") (pin "2") (pinfunction "2_2") (pintype "passive"))
    )
    (net (code "61") (name "Net-(IC66B-REGCAP1)") (class "Default")
      (node (ref "C569") (pin "2") (pinfunction "2_2") (pintype "passive"))
      (node (ref "C570") (pin "2") (pinfunction "2_2") (pintype "passive"))
      (node (ref "IC66") (pin "37") (pinfunction "REGCAP1_37") (pintype "passive"))
    )
    (net (code "62") (name "Net-(IC66B-REGCAP2)") (class "Default")
      (node (ref "C569") (pin "1") (pinfunction "1_1") (pintype "passive"))
      (node (ref "C570") (pin "1") (pinfunction "1_1") (pintype "passive"))
      (node (ref "IC66") (pin "41") (pinfunction "REGCAP2_41") (pintype "passive"))
    )
    (net (code "63") (name "Net-(LD14-C)") (class "Default")
      (node (ref "LD14") (pin "1") (pinfunction "C_1") (pintype "passive"))
      (node (ref "R365") (pin "2") (pinfunction "2_2") (pintype "passive"))
    )
    (net (code "64") (name "Net-(LD15-C)") (class "Default")
      (node (ref "LD15") (pin "1") (pinfunction "C_1") (pintype "passive"))
      (node (ref "R366") (pin "2") (pinfunction "2_2") (pintype "passive"))
    )
    (net (code "65") (name "Net-(LD16-A)") (class "Default")
      (node (ref "LD16") (pin "2") (pinfunction "A_2") (pintype "passive"))
      (node (ref "R508") (pin "1") (pinfunction "1_1") (pintype "passive"))
    )
    (net (code "66") (name "P3V3") (class "Default")
      (node (ref "C568") (pin "2") (pinfunction "2_2") (pintype "passive"))
      (node (ref "IC66") (pin "36") (pinfunction "REG_IN_36") (pintype "power_in"))
      (node (ref "L42") (pin "2") (pinfunction "2_2") (pintype "passive"))
      (node (ref "L43") (pin "2") (pinfunction "2_2") (pintype "passive"))
      (node (ref "LD14") (pin "2") (pinfunction "A_2") (pintype "passive"))
      (node (ref "LD15") (pin "2") (pinfunction "A_2") (pintype "passive"))
      (node (ref "R353") (pin "2") (pinfunction "2_2") (pintype "passive"))
      (node (ref "R361") (pin "2") (pinfunction "2_2") (pintype "passive"))
      (node (ref "R508") (pin "2") (pinfunction "2_2") (pintype "passive"))
    )
    (net (code "67") (name "unconnected-(IC66A-CLK125-Pad9)") (class "Default")
      (node (ref "IC66") (pin "9") (pinfunction "CLK125_9") (pintype "output"))
    )
    (net (code "68") (name "unconnected-(IC66A-HSDACN-Pad31)") (class "Default")
      (node (ref "IC66") (pin "31") (pinfunction "HSDACN_31") (pintype "output+no_connect"))
    )
    (net (code "69") (name "unconnected-(IC66A-HSDACP-Pad32)") (class "Default")
      (node (ref "IC66") (pin "32") (pinfunction "HSDACP_32") (pintype "output+no_connect"))
    )
    (net (code "70") (name "unconnected-(IC66A-TSTPT-Pad29)") (class "Default")
      (node (ref "IC66") (pin "29") (pinfunction "TSTPT_29") (pintype "output+no_connect"))
    )
    (net (code "71") (name "unconnected-(J17-Pad14)") (class "Default")
      (node (ref "J17") (pin "14") (pinfunction "14_14") (pintype "bidirectional"))
    )
  )
)
